# MIXED_FILTER.net
KiCad netlist of a schematic drawn in Altium Designer
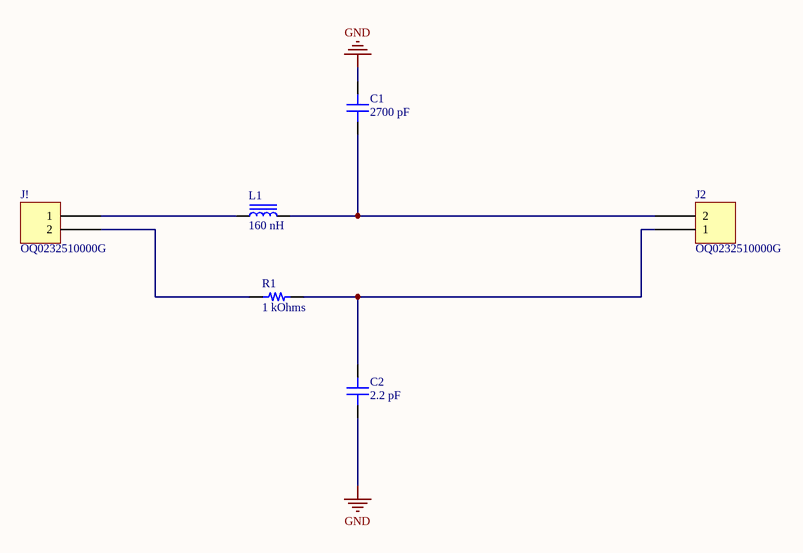
[diagram p0: MIXED_FILTER.SchDoc]

(export (version "E")
  (design (tool "Eeschema 10.0.6"))
  (components
    (comp (ref "C1")
      (value "2700 pF")
      (footprint "CAP 0603_1608")
      (description "CAP CER 2700PF 25V NP0 0603")
      (fields (field (name "PART NUMBER") "C0603C272F3GAC7867") (field (name "MANUFACTURER") "KEMET"))
      (libsource (lib "Celestial Altium Library - altium_library") (part "Capacitor"))
    )
    (comp (ref "C2")
      (value "2.2 pF")
      (footprint "CAP 0603_1608")
      (description "CAP CER 2.2PF 250V C0G/NP0 0603")
      (fields
        (field (name "PART NUMBER") "600S2R2AT250XT")
        (field (name "MANUFACTURER") "American Technical Ceramics")
      )
      (libsource (lib "Celestial Altium Library - altium_library") (part "Capacitor"))
    )
    (comp (ref "J!")
      (value "OQ0232510000G")
      (footprint "FCI 06-381-2PIN")
      (description "TERM BLOCK HDR 2POS 90DEG 3.81MM")
      (fields (field (name "MANUFACTURER") "Amphenol Anytek"))
      (libsource (lib "Celestial Altium Library - altium_library") (part "2 Pin"))
    )
    (comp (ref "J2")
      (value "OQ0232510000G")
      (footprint "FCI 06-381-2PIN")
      (description "TERM BLOCK HDR 2POS 90DEG 3.81MM")
      (fields (field (name "MANUFACTURER") "Amphenol Anytek"))
      (libsource (lib "") (part "2 Pin_1"))
    )
    (comp (ref "L1")
      (value "160 nH")
      (footprint "IND 0402_1005 RF WW")
      (description "FIXED IND 160NH 480MA 330MOHM SM")
      (fields
        (field (name "PART NUMBER") "LQW15CNR16J00D")
        (field (name "MANUFACTURER") "Murata Electronics")
      )
      (libsource (lib "Celestial Altium Library - altium_library") (part "Inductor"))
    )
    (comp (ref "R1")
      (value "1 kOhms")
      (footprint "RES 0603_1608")
      (description "RES SMD 1K OHM 0.1% 1/16W 0603")
      (fields
        (field (name "PART NUMBER") "CPF0603B1K0E")
        (field (name "MANUFACTURER") "TE Connectivity Passive Product")
      )
      (libsource (lib "Celestial Altium Library - altium_library") (part "Resistor"))
    )
  )
  (nets
    (net (code "1") (name "GND") (class "Default")
      (node (ref "C1") (pin "2") (pinfunction "2_2") (pintype "passive"))
      (node (ref "C2") (pin "2") (pinfunction "2_2") (pintype "passive"))
    )
    (net (code "2") (name "Net-(C1-Pad1)") (class "Default")
      (node (ref "C1") (pin "1") (pinfunction "1_1") (pintype "passive"))
      (node (ref "J2") (pin "2") (pinfunction "2_2") (pintype "passive"))
      (node (ref "L1") (pin "2") (pinfunction "2_2") (pintype "passive"))
    )
    (net (code "3") (name "Net-(C2-Pad1)") (class "Default")
      (node (ref "C2") (pin "1") (pinfunction "1_1") (pintype "passive"))
      (node (ref "J2") (pin "1") (pinfunction "1_1") (pintype "passive"))
      (node (ref "R1") (pin "2") (pinfunction "2_2") (pintype "passive"))
    )
    (net (code "4") (name "Net-(J!-Pad1)") (class "Default")
      (node (ref "J!") (pin "1") (pinfunction "1_1") (pintype "passive"))
      (node (ref "L1") (pin "1") (pinfunction "1_1") (pintype "passive"))
    )
    (net (code "5") (name "Net-(J!-Pad2)") (class "Default")
      (node (ref "J!") (pin "2") (pinfunction "2_2") (pintype "passive"))
      (node (ref "R1") (pin "1") (pinfunction "1_1") (pintype "passive"))
    )
  )
)
